# S3220A4.net
KiCad netlist of a schematic drawn in Altium Designer
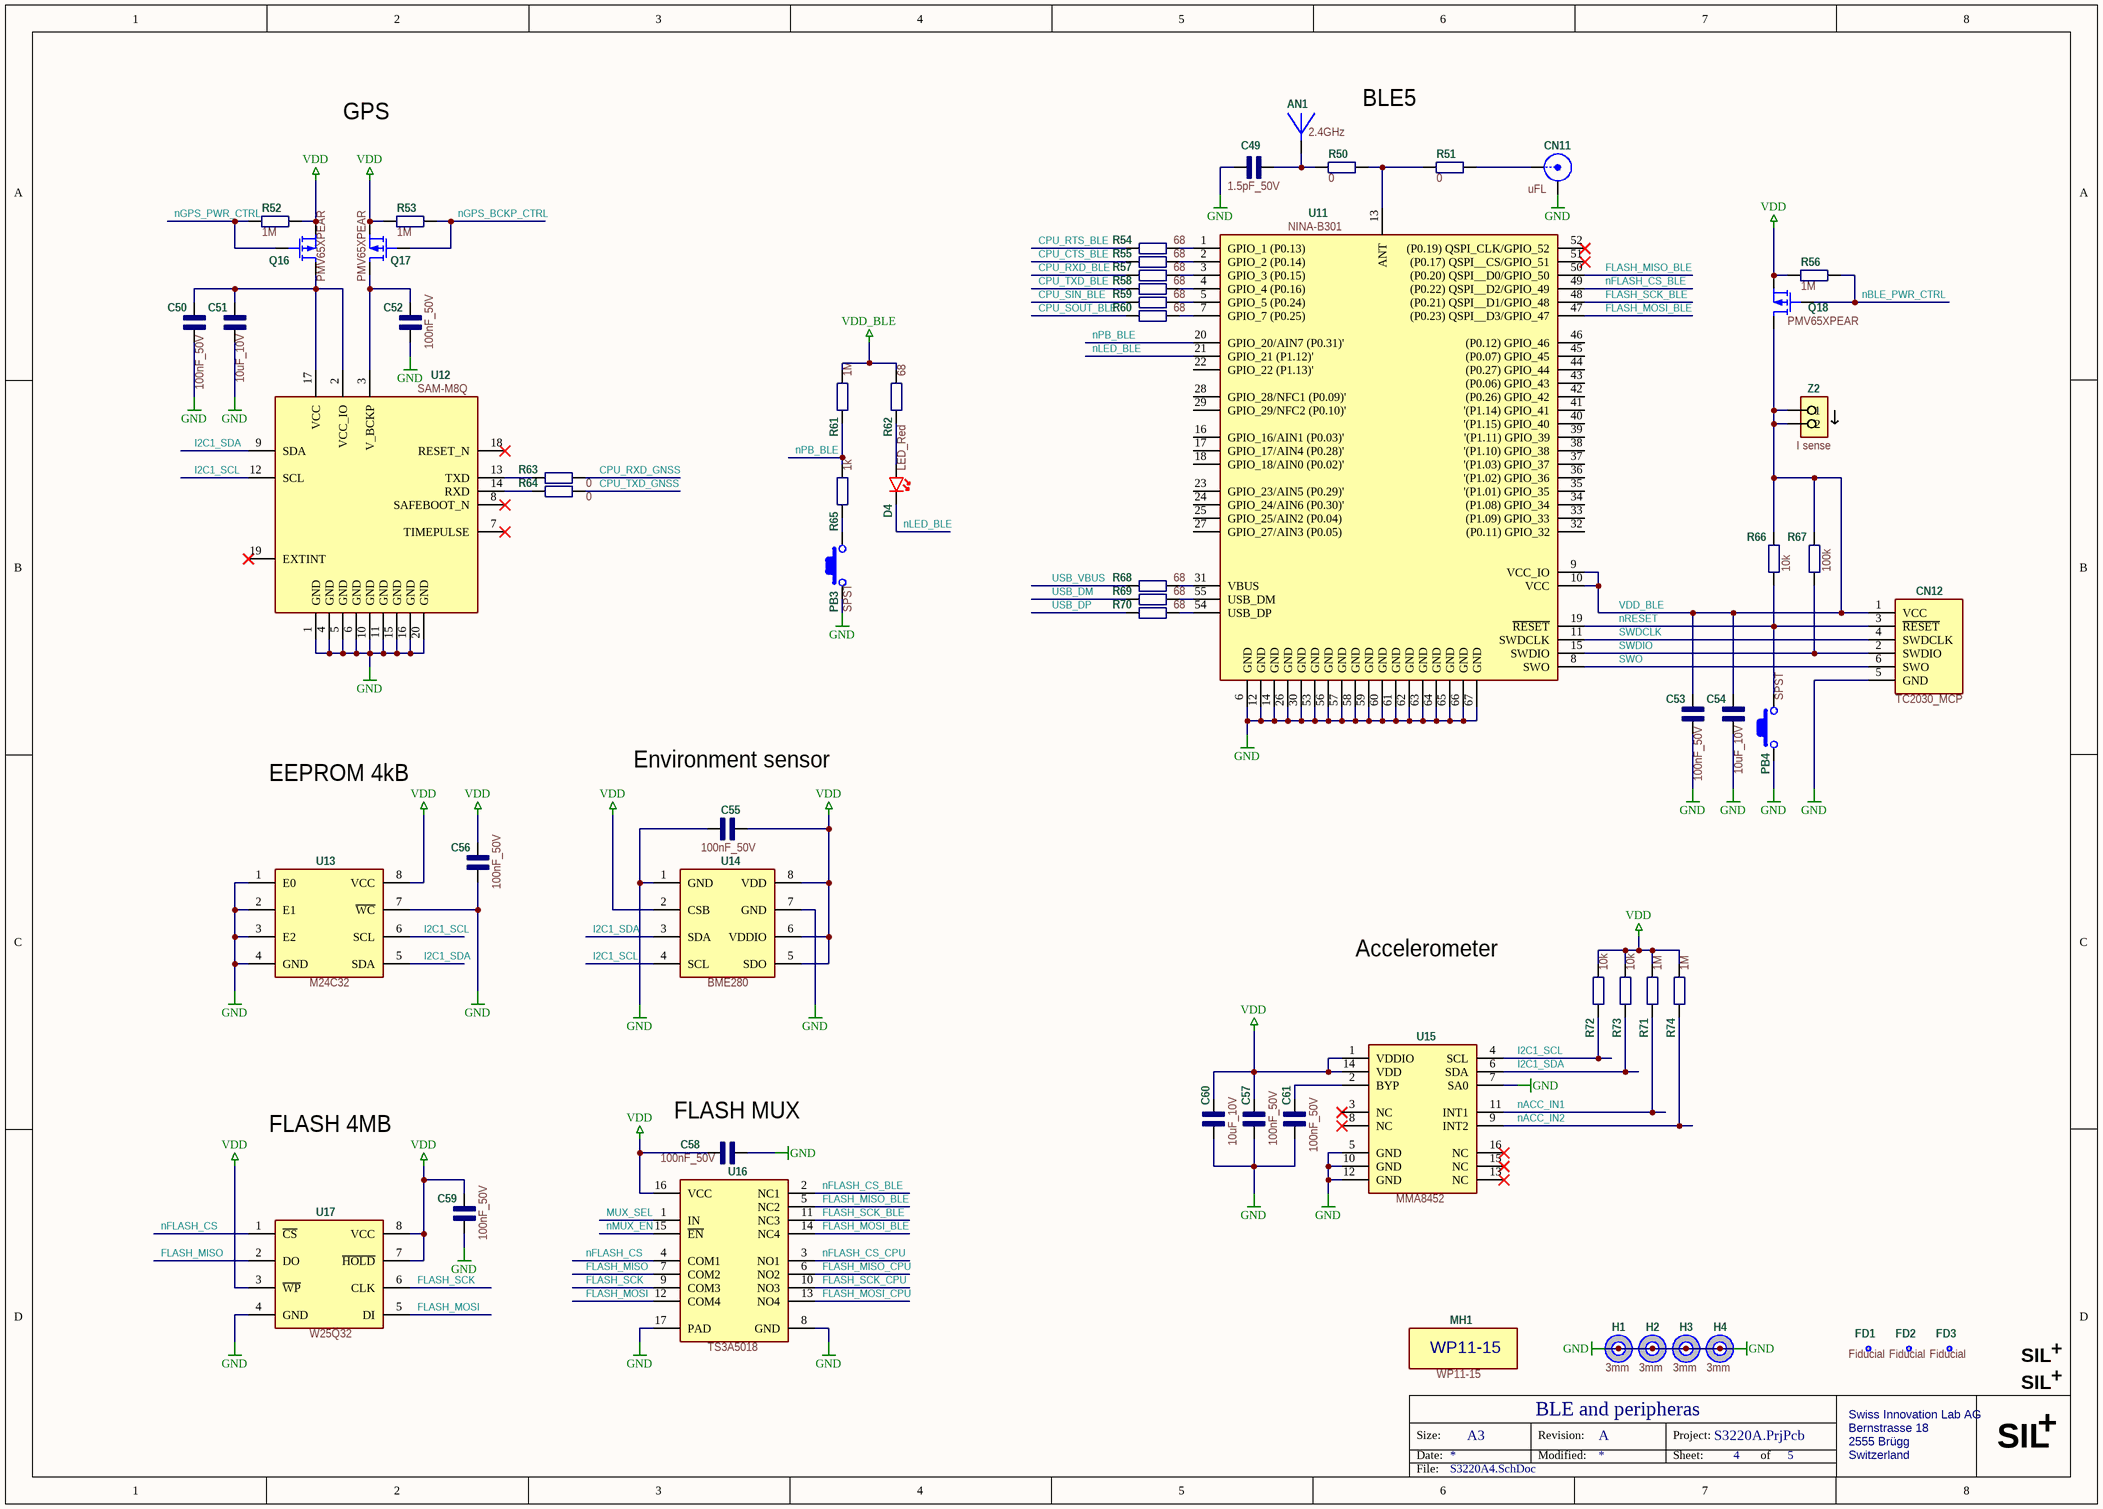
[diagram p0: S3220A4.SchDoc]

(export (version "E")
  (design (tool "Eeschema 10.0.6"))
  (components
    (comp (ref "AN1")
      (value "2.4GHz")
      (footprint "AN_2400-PCB-B")
      (description "2.4 GHz PCB antenna")
      (fields
        (field (name "MANUFACTURER") "Swiss Innovation Lab")
        (field (name "MANUFACTURER PART NUMBER") "SIL AN24GHZ")
      )
      (libsource (lib "SIL") (part "AN_2.4GHz-PCB"))
    )
    (comp (ref "C49")
      (value "1.5pF_50V")
      (footprint "SIL:C_0603")
      (description "1.5pF ±0.1pF 50V Ceramic Capacitor C0G, NP0 0603 (1608 Metric)")
      (fields
        (field (name "MANUFACTURER") "Samsung Electro-Mechanics")
        (field (name "MANUFACTURER PART NUMBER") "CL10C1R5BB8NNNC")
      )
      (libsource (lib "SIL") (part "C_1.5pF_50V"))
    )
    (comp (ref "C50")
      (value "100nF_50V")
      (footprint "SIL:C_0603")
      (description "0.1µF ±10% 50V Ceramic Capacitor X7R 0603 (1608 Metric)")
      (fields
        (field (name "MANUFACTURER") "TDK")
        (field (name "MANUFACTURER PART NUMBER") "C1608X7R1H104K080AA")
      )
      (libsource (lib "SIL") (part "C_100nF_50V"))
    )
    (comp (ref "C51")
      (value "10uF_10V")
      (footprint "SIL:C_0603")
      (description "10µF ±10% 10V Ceramic Capacitor X5R 0603 (1608 Metric)")
      (fields
        (field (name "MANUFACTURER") "Murata Electronics North America")
        (field (name "MANUFACTURER PART NUMBER") "GRM188R61A106KE69D")
      )
      (libsource (lib "SIL") (part "C_10uF_10V"))
    )
    (comp (ref "C52")
      (value "100nF_50V")
      (footprint "SIL:C_0603")
      (description "0.1µF ±10% 50V Ceramic Capacitor X7R 0603 (1608 Metric)")
      (fields
        (field (name "MANUFACTURER") "TDK")
        (field (name "MANUFACTURER PART NUMBER") "C1608X7R1H104K080AA")
      )
      (libsource (lib "SIL") (part "C_100nF_50V"))
    )
    (comp (ref "C53")
      (value "100nF_50V")
      (footprint "SIL:C_0603")
      (description "0.1µF ±10% 50V Ceramic Capacitor X7R 0603 (1608 Metric)")
      (fields
        (field (name "MANUFACTURER") "TDK")
        (field (name "MANUFACTURER PART NUMBER") "C1608X7R1H104K080AA")
      )
      (libsource (lib "SIL") (part "C_100nF_50V"))
    )
    (comp (ref "C54")
      (value "10uF_10V")
      (footprint "SIL:C_0603")
      (description "10µF ±10% 10V Ceramic Capacitor X5R 0603 (1608 Metric)")
      (fields
        (field (name "MANUFACTURER") "Murata Electronics North America")
        (field (name "MANUFACTURER PART NUMBER") "GRM188R61A106KE69D")
      )
      (libsource (lib "SIL") (part "C_10uF_10V"))
    )
    (comp (ref "C55")
      (value "100nF_50V")
      (footprint "SIL:C_0603")
      (description "0.1µF ±10% 50V Ceramic Capacitor X7R 0603 (1608 Metric)")
      (fields
        (field (name "MANUFACTURER") "TDK")
        (field (name "MANUFACTURER PART NUMBER") "C1608X7R1H104K080AA")
      )
      (libsource (lib "") (part "C_100nF_50V_3"))
    )
    (comp (ref "C56")
      (value "100nF_50V")
      (footprint "SIL:C_0603")
      (description "0.1µF ±10% 50V Ceramic Capacitor X7R 0603 (1608 Metric)")
      (fields
        (field (name "MANUFACTURER") "TDK")
        (field (name "MANUFACTURER PART NUMBER") "C1608X7R1H104K080AA")
      )
      (libsource (lib "SIL") (part "C_100nF_50V"))
    )
    (comp (ref "C57")
      (value "100nF_50V")
      (footprint "SIL:C_0603")
      (description "0.1µF ±10% 50V Ceramic Capacitor X7R 0603 (1608 Metric)")
      (fields
        (field (name "MANUFACTURER") "TDK")
        (field (name "MANUFACTURER PART NUMBER") "C1608X7R1H104K080AA")
      )
      (libsource (lib "") (part "C_100nF_50V_1"))
    )
    (comp (ref "C58")
      (value "100nF_50V")
      (footprint "SIL:C_0603")
      (description "0.1µF ±10% 50V Ceramic Capacitor X7R 0603 (1608 Metric)")
      (fields
        (field (name "MANUFACTURER") "TDK")
        (field (name "MANUFACTURER PART NUMBER") "C1608X7R1H104K080AA")
      )
      (libsource (lib "") (part "C_100nF_50V_2"))
    )
    (comp (ref "C59")
      (value "100nF_50V")
      (footprint "SIL:C_0603")
      (description "0.1µF ±10% 50V Ceramic Capacitor X7R 0603 (1608 Metric)")
      (fields
        (field (name "MANUFACTURER") "TDK")
        (field (name "MANUFACTURER PART NUMBER") "C1608X7R1H104K080AA")
      )
      (libsource (lib "SIL") (part "C_100nF_50V"))
    )
    (comp (ref "C60")
      (value "10uF_10V")
      (footprint "SIL:C_0603")
      (description "10µF ±10% 10V Ceramic Capacitor X5R 0603 (1608 Metric)")
      (fields
        (field (name "MANUFACTURER") "Murata Electronics North America")
        (field (name "MANUFACTURER PART NUMBER") "GRM188R61A106KE69D")
      )
      (libsource (lib "SIL") (part "C_10uF_10V"))
    )
    (comp (ref "C61")
      (value "100nF_50V")
      (footprint "SIL:C_0603")
      (description "0.1µF ±10% 50V Ceramic Capacitor X7R 0603 (1608 Metric)")
      (fields
        (field (name "MANUFACTURER") "TDK")
        (field (name "MANUFACTURER PART NUMBER") "C1608X7R1H104K080AA")
      )
      (libsource (lib "") (part "C_100nF_50V_1"))
    )
    (comp (ref "CN11")
      (value "uFL")
      (footprint "CN_RF_uFL")
      (description "Ultra Miniature Coaxial Connector Jack, Male Pin 50 Ohm Surface Mount Solder")
      (fields
        (field (name "MANUFACTURER") "TE Connectivity AMP Connectors")
        (field (name "MANUFACTURER PART NUMBER") "1909763-1")
      )
      (libsource (lib "SIL") (part "CN_RF_uFL"))
    )
    (comp (ref "CN12")
      (value "TC2030_MCP")
      (footprint "SIL:CN_TC2030-MCP-NL")
      (description "TC2030-MCP-NL")
      (libsource (lib "SIL") (part "CN_TC2030"))
    )
    (comp (ref "D4")
      (value "LED_Red")
      (footprint "LED_0603")
      (description "Red 631nm LED Indication - Discrete 2V 0603")
      (fields
        (field (name "MANUFACTURER") "Lite-On Inc.")
        (field (name "MANUFACTURER PART NUMBER") "LTST-C193KRKT-5A")
      )
      (libsource (lib "SIL") (part "D_LED_R_5mA"))
    )
    (comp (ref "FD1")
      (value "Fiducial")
      (footprint "FD_Fiducial")
      (description "Reference point for assembly machine")
      (fields (field (name "MANUFACTURER") "Swiss Innovation Lab"))
      (libsource (lib "SIL") (part "FD_Fiducial"))
    )
    (comp (ref "FD2")
      (value "Fiducial")
      (footprint "FD_Fiducial")
      (description "Reference point for assembly machine")
      (fields (field (name "MANUFACTURER") "Swiss Innovation Lab"))
      (libsource (lib "SIL") (part "FD_Fiducial"))
    )
    (comp (ref "FD3")
      (value "Fiducial")
      (footprint "FD_Fiducial")
      (description "Reference point for assembly machine")
      (fields (field (name "MANUFACTURER") "Swiss Innovation Lab"))
      (libsource (lib "SIL") (part "FD_Fiducial"))
    )
    (comp (ref "H1")
      (value "3mm")
      (footprint "H_3M_55M")
      (description "Hole 3mm, Pad 5.5mm")
      (fields (field (name "MANUFACTURER") "Swissinnolab"))
      (libsource (lib "Swissinnovationlab") (part "H_3M_55M"))
    )
    (comp (ref "H2")
      (value "3mm")
      (footprint "H_3M_55M")
      (description "Hole 3mm, Pad 5.5mm")
      (fields (field (name "MANUFACTURER") "Swissinnolab"))
      (libsource (lib "Swissinnovationlab") (part "H_3M_55M"))
    )
    (comp (ref "H3")
      (value "3mm")
      (footprint "H_3M_55M")
      (description "Hole 3mm, Pad 5.5mm")
      (fields (field (name "MANUFACTURER") "Swissinnolab"))
      (libsource (lib "Swissinnovationlab") (part "H_3M_55M"))
    )
    (comp (ref "H4")
      (value "3mm")
      (footprint "H_3M_55M")
      (description "Hole 3mm, Pad 5.5mm")
      (fields (field (name "MANUFACTURER") "Swissinnolab"))
      (libsource (lib "Swissinnovationlab") (part "H_3M_55M"))
    )
    (comp (ref "MH1")
      (value "WP11-15")
      (footprint "MH_WP11-15")
      (description "Case Takachi WP11-15")
      (fields (field (name "MANUFACTURER") "Takachi"))
      (libsource (lib "SIL") (part "MH_WP11-15"))
    )
    (comp (ref "PB3")
      (value "SPST")
      (footprint "SIL:PB_PTS810")
      (description "Tactile Switch SPST-NO Top Actuated Surface Mount")
      (fields
        (field (name "MANUFACTURER") "C&K")
        (field (name "MANUFACTURER PART NUMBER") "PTS810 SJM 250 SMTR LFS")
      )
      (libsource (lib "SIL") (part "PB_SPST_2.5mm"))
    )
    (comp (ref "PB4")
      (value "SPST")
      (footprint "SIL:PB_PTS810")
      (description "Tactile Switch SPST-NO Top Actuated Surface Mount")
      (fields
        (field (name "MANUFACTURER") "C&K")
        (field (name "MANUFACTURER PART NUMBER") "PTS810 SJM 250 SMTR LFS")
      )
      (libsource (lib "SIL") (part "PB_SPST_2.5mm"))
    )
    (comp (ref "Q16")
      (value "PMV65XPEAR")
      (footprint "U_SOT23-3")
      (description "P-Channel 20V 2.8A (Ta) 480mW (Ta), 6.25W (Tc) Surface Mount TO-236AB (SOT23)")
      (fields (field (name "MANUFACTURER") "Nexperia USA Inc."))
      (libsource (lib "SIL") (part "Q_PMV65"))
    )
    (comp (ref "Q17")
      (value "PMV65XPEAR")
      (footprint "U_SOT23-3")
      (description "P-Channel 20V 2.8A (Ta) 480mW (Ta), 6.25W (Tc) Surface Mount TO-236AB (SOT23)")
      (fields (field (name "MANUFACTURER") "Nexperia USA Inc."))
      (libsource (lib "SIL") (part "Q_PMV65"))
    )
    (comp (ref "Q18")
      (value "PMV65XPEAR")
      (footprint "U_SOT23-3")
      (description "P-Channel 20V 2.8A (Ta) 480mW (Ta), 6.25W (Tc) Surface Mount TO-236AB (SOT23)")
      (fields (field (name "MANUFACTURER") "Nexperia USA Inc."))
      (libsource (lib "SIL") (part "Q_PMV65"))
    )
    (comp (ref "R50")
      (value "0")
      (footprint "SIL:R_0603")
      (description "0 Ohms Jumper 0.1W, 1/10W Chip Resistor 0603 (1608 Metric) Automotive AEC-Q200 Thick Film")
      (fields
        (field (name "MANUFACTURER") "Panasonic Electronic Components")
        (field (name "MANUFACTURER PART NUMBER") "ERJ-3GEY0R00V")
      )
      (libsource (lib "SIL") (part "R_0_1%"))
    )
    (comp (ref "R51")
      (value "0")
      (footprint "SIL:R_0603")
      (description "0 Ohms Jumper 0.1W, 1/10W Chip Resistor 0603 (1608 Metric) Automotive AEC-Q200 Thick Film")
      (fields
        (field (name "MANUFACTURER") "Panasonic Electronic Components")
        (field (name "MANUFACTURER PART NUMBER") "ERJ-3GEY0R00V")
      )
      (libsource (lib "SIL") (part "R_0_1%"))
    )
    (comp (ref "R52")
      (value "1M")
      (footprint "SIL:R_0603")
      (description "1 MOhms ±1% 0.1W, 1/10W Chip Resistor 0603 (1608 Metric) Automotive AEC-Q200 Thick Film")
      (fields
        (field (name "MANUFACTURER") "Panasonic Electronic Components")
        (field (name "MANUFACTURER PART NUMBER") "ERJ-3EKF1004V")
      )
      (libsource (lib "") (part "R_1M_1%_2"))
    )
    (comp (ref "R53")
      (value "1M")
      (footprint "SIL:R_0603")
      (description "1 MOhms ±1% 0.1W, 1/10W Chip Resistor 0603 (1608 Metric) Automotive AEC-Q200 Thick Film")
      (fields
        (field (name "MANUFACTURER") "Panasonic Electronic Components")
        (field (name "MANUFACTURER PART NUMBER") "ERJ-3EKF1004V")
      )
      (libsource (lib "") (part "R_1M_1%_1"))
    )
    (comp (ref "R54")
      (value "68")
      (footprint "SIL:R_0603")
      (description "68 Ohms ±1% 0.1W, 1/10W Chip Resistor 0603 (1608 Metric) Automotive AEC-Q200 Thick Film")
      (fields
        (field (name "MANUFACTURER") "Panasonic Electronic Components")
        (field (name "MANUFACTURER PART NUMBER") "ERJ-3EKF68R0V")
      )
      (libsource (lib "SIL") (part "R_68_1%"))
    )
    (comp (ref "R55")
      (value "68")
      (footprint "SIL:R_0603")
      (description "68 Ohms ±1% 0.1W, 1/10W Chip Resistor 0603 (1608 Metric) Automotive AEC-Q200 Thick Film")
      (fields
        (field (name "MANUFACTURER") "Panasonic Electronic Components")
        (field (name "MANUFACTURER PART NUMBER") "ERJ-3EKF68R0V")
      )
      (libsource (lib "SIL") (part "R_68_1%"))
    )
    (comp (ref "R56")
      (value "1M")
      (footprint "SIL:R_0603")
      (description "1 MOhms ±1% 0.1W, 1/10W Chip Resistor 0603 (1608 Metric) Automotive AEC-Q200 Thick Film")
      (fields
        (field (name "MANUFACTURER") "Panasonic Electronic Components")
        (field (name "MANUFACTURER PART NUMBER") "ERJ-3EKF1004V")
      )
      (libsource (lib "") (part "R_1M_1%_1"))
    )
    (comp (ref "R57")
      (value "68")
      (footprint "SIL:R_0603")
      (description "68 Ohms ±1% 0.1W, 1/10W Chip Resistor 0603 (1608 Metric) Automotive AEC-Q200 Thick Film")
      (fields
        (field (name "MANUFACTURER") "Panasonic Electronic Components")
        (field (name "MANUFACTURER PART NUMBER") "ERJ-3EKF68R0V")
      )
      (libsource (lib "SIL") (part "R_68_1%"))
    )
    (comp (ref "R58")
      (value "68")
      (footprint "SIL:R_0603")
      (description "68 Ohms ±1% 0.1W, 1/10W Chip Resistor 0603 (1608 Metric) Automotive AEC-Q200 Thick Film")
      (fields
        (field (name "MANUFACTURER") "Panasonic Electronic Components")
        (field (name "MANUFACTURER PART NUMBER") "ERJ-3EKF68R0V")
      )
      (libsource (lib "SIL") (part "R_68_1%"))
    )
    (comp (ref "R59")
      (value "68")
      (footprint "SIL:R_0603")
      (description "68 Ohms ±1% 0.1W, 1/10W Chip Resistor 0603 (1608 Metric) Automotive AEC-Q200 Thick Film")
      (fields
        (field (name "MANUFACTURER") "Panasonic Electronic Components")
        (field (name "MANUFACTURER PART NUMBER") "ERJ-3EKF68R0V")
      )
      (libsource (lib "SIL") (part "R_68_1%"))
    )
    (comp (ref "R60")
      (value "68")
      (footprint "SIL:R_0603")
      (description "68 Ohms ±1% 0.1W, 1/10W Chip Resistor 0603 (1608 Metric) Automotive AEC-Q200 Thick Film")
      (fields
        (field (name "MANUFACTURER") "Panasonic Electronic Components")
        (field (name "MANUFACTURER PART NUMBER") "ERJ-3EKF68R0V")
      )
      (libsource (lib "SIL") (part "R_68_1%"))
    )
    (comp (ref "R61")
      (value "1M")
      (footprint "SIL:R_0603")
      (description "1 MOhms ±1% 0.1W, 1/10W Chip Resistor 0603 (1608 Metric) Automotive AEC-Q200 Thick Film")
      (fields
        (field (name "MANUFACTURER") "Panasonic Electronic Components")
        (field (name "MANUFACTURER PART NUMBER") "ERJ-3EKF1004V")
      )
      (libsource (lib "SIL") (part "R_1M_1%"))
    )
    (comp (ref "R62")
      (value "68")
      (footprint "SIL:R_0603")
      (description "68 Ohms ±1% 0.1W, 1/10W Chip Resistor 0603 (1608 Metric) Automotive AEC-Q200 Thick Film")
      (fields
        (field (name "MANUFACTURER") "Panasonic Electronic Components")
        (field (name "MANUFACTURER PART NUMBER") "ERJ-3EKF68R0V")
      )
      (libsource (lib "") (part "R_68_1%_1"))
    )
    (comp (ref "R63")
      (value "0")
      (footprint "SIL:R_0603")
      (description "0 Ohms Jumper 0.1W, 1/10W Chip Resistor 0603 (1608 Metric) Automotive AEC-Q200 Thick Film")
      (fields
        (field (name "MANUFACTURER") "Panasonic Electronic Components")
        (field (name "MANUFACTURER PART NUMBER") "ERJ-3GEY0R00V")
      )
      (libsource (lib "SIL") (part "R_0_1%"))
    )
    (comp (ref "R64")
      (value "0")
      (footprint "SIL:R_0603")
      (description "0 Ohms Jumper 0.1W, 1/10W Chip Resistor 0603 (1608 Metric) Automotive AEC-Q200 Thick Film")
      (fields
        (field (name "MANUFACTURER") "Panasonic Electronic Components")
        (field (name "MANUFACTURER PART NUMBER") "ERJ-3GEY0R00V")
      )
      (libsource (lib "SIL") (part "R_0_1%"))
    )
    (comp (ref "R65")
      (value "1k")
      (footprint "SIL:R_0603")
      (description "1 kOhms ±1% 0.1W, 1/10W Chip Resistor 0603 (1608 Metric) Automotive AEC-Q200 Thick Film")
      (fields
        (field (name "MANUFACTURER") "Panasonic Electronic Components")
        (field (name "MANUFACTURER PART NUMBER") "ERJ-3EKF1001V")
      )
      (libsource (lib "SIL") (part "R_1k_1%"))
    )
    (comp (ref "R66")
      (value "10k")
      (footprint "SIL:R_0603")
      (description "10 kOhms ±1% 0.1W, 1/10W Chip Resistor 0603 (1608 Metric) Automotive AEC-Q200 Thick Film")
      (fields
        (field (name "MANUFACTURER") "Panasonic Electronic Components")
        (field (name "MANUFACTURER PART NUMBER") "ERJ-3EKF1002V")
      )
      (libsource (lib "SIL") (part "R_10k_1%"))
    )
    (comp (ref "R67")
      (value "100k")
      (footprint "SIL:R_0603")
      (description "100 kOhms ±1% 0.1W, 1/10W Chip Resistor 0603 (1608 Metric) Automotive AEC-Q200 Thick Film")
      (fields
        (field (name "MANUFACTURER") "Panasonic Electronic Components")
        (field (name "MANUFACTURER PART NUMBER") "ERJ-3EKF1003V")
      )
      (libsource (lib "SIL") (part "R_100k_1%"))
    )
    (comp (ref "R68")
      (value "68")
      (footprint "SIL:R_0603")
      (description "68 Ohms ±1% 0.1W, 1/10W Chip Resistor 0603 (1608 Metric) Automotive AEC-Q200 Thick Film")
      (fields
        (field (name "MANUFACTURER") "Panasonic Electronic Components")
        (field (name "MANUFACTURER PART NUMBER") "ERJ-3EKF68R0V")
      )
      (libsource (lib "SIL") (part "R_68_1%"))
    )
    (comp (ref "R69")
      (value "68")
      (footprint "SIL:R_0603")
      (description "68 Ohms ±1% 0.1W, 1/10W Chip Resistor 0603 (1608 Metric) Automotive AEC-Q200 Thick Film")
      (fields
        (field (name "MANUFACTURER") "Panasonic Electronic Components")
        (field (name "MANUFACTURER PART NUMBER") "ERJ-3EKF68R0V")
      )
      (libsource (lib "SIL") (part "R_68_1%"))
    )
    (comp (ref "R70")
      (value "68")
      (footprint "SIL:R_0603")
      (description "68 Ohms ±1% 0.1W, 1/10W Chip Resistor 0603 (1608 Metric) Automotive AEC-Q200 Thick Film")
      (fields
        (field (name "MANUFACTURER") "Panasonic Electronic Components")
        (field (name "MANUFACTURER PART NUMBER") "ERJ-3EKF68R0V")
      )
      (libsource (lib "SIL") (part "R_68_1%"))
    )
    (comp (ref "R71")
      (value "1M")
      (footprint "SIL:R_0603")
      (description "1 MOhms ±1% 0.1W, 1/10W Chip Resistor 0603 (1608 Metric) Automotive AEC-Q200 Thick Film")
      (fields
        (field (name "MANUFACTURER") "Panasonic Electronic Components")
        (field (name "MANUFACTURER PART NUMBER") "ERJ-3EKF1004V")
      )
      (libsource (lib "SIL") (part "R_1M_1%"))
    )
    (comp (ref "R72")
      (value "10k")
      (footprint "SIL:R_0603")
      (description "10 kOhms ±1% 0.1W, 1/10W Chip Resistor 0603 (1608 Metric) Automotive AEC-Q200 Thick Film")
      (fields
        (field (name "MANUFACTURER") "Panasonic Electronic Components")
        (field (name "MANUFACTURER PART NUMBER") "ERJ-3EKF1002V")
      )
      (libsource (lib "SIL") (part "R_10k_1%"))
    )
    (comp (ref "R73")
      (value "10k")
      (footprint "SIL:R_0603")
      (description "10 kOhms ±1% 0.1W, 1/10W Chip Resistor 0603 (1608 Metric) Automotive AEC-Q200 Thick Film")
      (fields
        (field (name "MANUFACTURER") "Panasonic Electronic Components")
        (field (name "MANUFACTURER PART NUMBER") "ERJ-3EKF1002V")
      )
      (libsource (lib "SIL") (part "R_10k_1%"))
    )
    (comp (ref "R74")
      (value "1M")
      (footprint "SIL:R_0603")
      (description "1 MOhms ±1% 0.1W, 1/10W Chip Resistor 0603 (1608 Metric) Automotive AEC-Q200 Thick Film")
      (fields
        (field (name "MANUFACTURER") "Panasonic Electronic Components")
        (field (name "MANUFACTURER PART NUMBER") "ERJ-3EKF1004V")
      )
      (libsource (lib "SIL") (part "R_1M_1%"))
    )
    (comp (ref "U11")
      (value "NINA-B301")
      (footprint "U_NINA-B301")
      (description "MOD BLE 4.2 NORDIC NRF52840 SOC")
      (fields (field (name "MANUFACTURER") "uBlox"))
      (libsource (lib "SIL") (part "U_NINA-B301"))
    )
    (comp (ref "U12")
      (value "SAM-M8Q")
      (footprint "U_SAM-M8Q")
      (description "SAM-M8Q RF Receiver Galileo, GLONASS, GPS 1.575GHz, 1.602GHz -165dBm 400kbps")
      (fields
        (field (name "MANUFACTURER") "U-Blox America Inc.")
        (field (name "MANUFACTURER PART NUMBER") "SAM-M8Q-0-10")
      )
      (libsource (lib "SIL") (part "U_SAM-M8Q"))
    )
    (comp (ref "U13")
      (value "M24C32")
      (footprint "U_8-SOIC_3.9")
      (description "EEPROM Memory IC 32Kb (4K x 8) I2C 1MHz 450ns 8-SO")
      (fields
        (field (name "MANUFACTURER") "STMicroelectronics")
        (field (name "MANUFACTURER PART NUMBER") "M24C32-WMN6TP")
      )
      (libsource (lib "SIL") (part "U_M24C32"))
    )
    (comp (ref "U14")
      (value "BME280")
      (footprint "SIL:U_BME280")
      (description "Humidity Temperature Sensor 0 ~ 100% RH I2C, SPI ±3% 1s Surface Mount")
      (fields (field (name "MANUFACTURER") "Bosch Sensortec"))
      (libsource (lib "SIL") (part "U_BME280"))
    )
    (comp (ref "U15")
      (value "MMA8452")
      (footprint "U_16-QFN-5X3")
      (description "Accelerometer X, Y, Z Axis ±2g, 4g, 8g 0.78Hz ~ 400Hz 16-QFN (3x3)")
      (fields
        (field (name "MANUFACTURER") "NXP USA Inc.")
        (field (name "MANUFACTURER PART NUMBER") "MMA8452QT")
      )
      (libsource (lib "SIL") (part "U_MMA8452"))
    )
    (comp (ref "U16")
      (value "TS3A5018")
      (footprint "U_16-VFQFN")
      (description "4 Circuit IC Switch 2:1 10Ohm 16-UQFN (2.6x1.8)")
      (fields
        (field (name "MANUFACTURER") "Texas Instruments")
        (field (name "MANUFACTURER PART NUMBER") "TS3A5018RGYR")
      )
      (libsource (lib "SIL") (part "U_TS3A5018"))
    )
    (comp (ref "U17")
      (value "W25Q32")
      (footprint "U_8-SOIC_5.3")
      (description "FLASH - NOR Memory IC 32Mb (4M x 8) SPI - Quad I/O 133MHz  8-SOIC")
      (fields
        (field (name "MANUFACTURER") "Winbond Electronics")
        (field (name "MANUFACTURER PART NUMBER") "W25Q32JVSSIQ")
      )
      (libsource (lib "SIL") (part "U_W25Q32"))
    )
    (comp (ref "Z2")
      (value "I sense")
      (footprint "Z_I_SENSE")
      (description "2 Positions Header Connector 0.100\" (2.54mm) SMD Gold for current measurement")
      (fields (field (name "MANUFACTURER") "SIL"))
      (libsource (lib "SIL") (part "Z_I_sense"))
    )
    (comp (ref "Z3")
      (value "SIL logo")
      (footprint "Z_SIL-logo")
      (fields
        (field (name "MANUFACTURER") "Swiss Innovation Lab")
        (field (name "MANUFACTURER PART NUMBER") "SIL Logo")
      )
      (libsource (lib "SIL") (part "Z_SIL_logo"))
    )
    (comp (ref "Z4")
      (value "SIL logo")
      (footprint "Z_SIL-logo")
      (fields
        (field (name "MANUFACTURER") "Swiss Innovation Lab")
        (field (name "MANUFACTURER PART NUMBER") "SIL Logo")
      )
      (libsource (lib "SIL") (part "Z_SIL_logo"))
    )
  )
  (nets
    (net (code "1") (name "/CPU_CTS_BLE") (class "Default")
      (node (ref "R55") (pin "1") (pinfunction "1_1") (pintype "passive"))
    )
    (net (code "2") (name "/CPU_RTS_BLE") (class "Default")
      (node (ref "R54") (pin "1") (pinfunction "1_1") (pintype "passive"))
    )
    (net (code "3") (name "/CPU_RXD_BLE") (class "Default")
      (node (ref "R57") (pin "1") (pinfunction "1_1") (pintype "passive"))
    )
    (net (code "4") (name "/CPU_RXD_GNSS") (class "Default")
      (node (ref "R63") (pin "2") (pinfunction "2_2") (pintype "passive"))
    )
    (net (code "5") (name "/CPU_SIN_BLE") (class "Default")
      (node (ref "R59") (pin "1") (pinfunction "1_1") (pintype "passive"))
    )
    (net (code "6") (name "/CPU_SOUT_BLE") (class "Default")
      (node (ref "R60") (pin "1") (pinfunction "1_1") (pintype "passive"))
    )
    (net (code "7") (name "/CPU_TXD_BLE") (class "Default")
      (node (ref "R58") (pin "1") (pinfunction "1_1") (pintype "passive"))
    )
    (net (code "8") (name "/CPU_TXD_GNSS") (class "Default")
      (node (ref "R64") (pin "2") (pinfunction "2_2") (pintype "passive"))
    )
    (net (code "9") (name "/FLASH_MISO") (class "Default")
      (node (ref "U16") (pin "7") (pinfunction "COM2_7") (pintype "passive"))
      (node (ref "U17") (pin "2") (pinfunction "DO_2") (pintype "passive"))
    )
    (net (code "10") (name "/FLASH_MISO_BLE") (class "Default")
      (node (ref "U11") (pin "50") (pinfunction "(P0.20)_QSPI__D0/GPIO_50_50") (pintype "passive"))
      (node (ref "U16") (pin "5") (pinfunction "NC2_5") (pintype "passive"))
    )
    (net (code "11") (name "/FLASH_MISO_CPU") (class "Default")
      (node (ref "U16") (pin "6") (pinfunction "NO2_6") (pintype "passive"))
    )
    (net (code "12") (name "/FLASH_MOSI") (class "Default")
      (node (ref "U16") (pin "12") (pinfunction "COM4_12") (pintype "passive"))
      (node (ref "U17") (pin "5") (pinfunction "DI_5") (pintype "passive"))
    )
    (net (code "13") (name "/FLASH_MOSI_BLE") (class "Default")
      (node (ref "U11") (pin "47") (pinfunction "(P0.23)_QSPI__D3/GPIO_47_47") (pintype "passive"))
      (node (ref "U16") (pin "14") (pinfunction "NC4_14") (pintype "passive"))
    )
    (net (code "14") (name "/FLASH_MOSI_CPU") (class "Default")
      (node (ref "U16") (pin "13") (pinfunction "NO4_13") (pintype "passive"))
    )
    (net (code "15") (name "/FLASH_SCK") (class "Default")
      (node (ref "U16") (pin "9") (pinfunction "COM3_9") (pintype "passive"))
      (node (ref "U17") (pin "6") (pinfunction "CLK_6") (pintype "passive"))
    )
    (net (code "16") (name "/FLASH_SCK_BLE") (class "Default")
      (node (ref "U11") (pin "48") (pinfunction "(P0.21)_QSPI__D1/GPIO_48_48") (pintype "passive"))
      (node (ref "U16") (pin "11") (pinfunction "NC3_11") (pintype "passive"))
    )
    (net (code "17") (name "/FLASH_SCK_CPU") (class "Default")
      (node (ref "U16") (pin "10") (pinfunction "NO3_10") (pintype "passive"))
    )
    (net (code "18") (name "/I2C1_SCL") (class "Default")
      (node (ref "R72") (pin "1") (pinfunction "1_1") (pintype "passive"))
      (node (ref "U12") (pin "12") (pinfunction "SCL_12") (pintype "passive"))
      (node (ref "U13") (pin "6") (pinfunction "SCL_6") (pintype "passive"))
      (node (ref "U14") (pin "4") (pinfunction "SCL_4") (pintype "passive"))
      (node (ref "U15") (pin "4") (pinfunction "SCL_4") (pintype "passive"))
    )
    (net (code "19") (name "/I2C1_SDA") (class "Default")
      (node (ref "R73") (pin "1") (pinfunction "1_1") (pintype "passive"))
      (node (ref "U12") (pin "9") (pinfunction "SDA_9") (pintype "passive"))
      (node (ref "U13") (pin "5") (pinfunction "SDA_5") (pintype "passive"))
      (node (ref "U14") (pin "3") (pinfunction "SDA_3") (pintype "passive"))
      (node (ref "U15") (pin "6") (pinfunction "SDA_6") (pintype "passive"))
    )
    (net (code "20") (name "/MUX_SEL") (class "Default")
      (node (ref "U16") (pin "1") (pinfunction "IN_1") (pintype "passive"))
    )
    (net (code "21") (name "/SWDCLK") (class "Default")
      (node (ref "CN12") (pin "4") (pinfunction "SWDCLK_4") (pintype "passive"))
      (node (ref "U11") (pin "11") (pinfunction "SWDCLK_11") (pintype "passive"))
    )
    (net (code "22") (name "/SWDIO") (class "Default")
      (node (ref "CN12") (pin "2") (pinfunction "SWDIO_2") (pintype "passive"))
      (node (ref "R67") (pin "1") (pinfunction "1_1") (pintype "passive"))
      (node (ref "U11") (pin "15") (pinfunction "SWDIO_15") (pintype "passive"))
    )
    (net (code "23") (name "/SWO") (class "Default")
      (node (ref "CN12") (pin "6") (pinfunction "SWO_6") (pintype "passive"))
      (node (ref "U11") (pin "8") (pinfunction "SWO_8") (pintype "passive"))
    )
    (net (code "24") (name "/USB_DM") (class "Default")
      (node (ref "R69") (pin "1") (pinfunction "1_1") (pintype "passive"))
    )
    (net (code "25") (name "/USB_DP") (class "Default")
      (node (ref "R70") (pin "1") (pinfunction "1_1") (pintype "passive"))
    )
    (net (code "26") (name "/USB_VBUS") (class "Default")
      (node (ref "R68") (pin "1") (pinfunction "1_1") (pintype "passive"))
    )
    (net (code "27") (name "/nACC_IN1") (class "Default")
      (node (ref "R71") (pin "2") (pinfunction "2_2") (pintype "passive"))
      (node (ref "U15") (pin "11") (pinfunction "INT1_11") (pintype "passive"))
    )
    (net (code "28") (name "/nACC_IN2") (class "Default")
      (node (ref "R74") (pin "2") (pinfunction "2_2") (pintype "passive"))
      (node (ref "U15") (pin "9") (pinfunction "INT2_9") (pintype "passive"))
    )
    (net (code "29") (name "/nBLE_PWR_CTRL") (class "Default")
      (node (ref "Q18") (pin "1") (pinfunction "G_1") (pintype "passive"))
      (node (ref "R56") (pin "1") (pinfunction "1_1") (pintype "passive"))
    )
    (net (code "30") (name "/nFLASH_CS") (class "Default")
      (node (ref "U16") (pin "4") (pinfunction "COM1_4") (pintype "passive"))
      (node (ref "U17") (pin "1") (pinfunction "~{CS}_1") (pintype "passive"))
    )
    (net (code "31") (name "/nFLASH_CS_BLE") (class "Default")
      (node (ref "U11") (pin "49") (pinfunction "(P0.22)_QSPI__D2/GPIO_49_49") (pintype "passive"))
      (node (ref "U16") (pin "2") (pinfunction "NC1_2") (pintype "passive"))
    )
    (net (code "32") (name "/nFLASH_CS_CPU") (class "Default")
      (node (ref "U16") (pin "3") (pinfunction "NO1_3") (pintype "passive"))
    )
    (net (code "33") (name "/nGPS_BCKP_CTRL") (class "Default")
      (node (ref "Q17") (pin "1") (pinfunction "G_1") (pintype "passive"))
      (node (ref "R53") (pin "1") (pinfunction "1_1") (pintype "passive"))
    )
    (net (code "34") (name "/nGPS_PWR_CTRL") (class "Default")
      (node (ref "Q16") (pin "1") (pinfunction "G_1") (pintype "passive"))
      (node (ref "R52") (pin "1") (pinfunction "1_1") (pintype "passive"))
    )
    (net (code "35") (name "/nLED_BLE") (class "Default")
      (node (ref "D4") (pin "2") (pinfunction "K_2") (pintype "passive"))
      (node (ref "U11") (pin "21") (pinfunction "GPIO_21_(P1.12)'_21") (pintype "passive"))
    )
    (net (code "36") (name "/nMUX_EN") (class "Default")
      (node (ref "U16") (pin "15") (pinfunction "~{EN}_15") (pintype "passive"))
    )
    (net (code "37") (name "/nPB_BLE") (class "Default")
      (node (ref "R61") (pin "2") (pinfunction "2_2") (pintype "passive"))
      (node (ref "R65") (pin "2") (pinfunction "2_2") (pintype "passive"))
      (node (ref "U11") (pin "20") (pinfunction "GPIO_20/AIN7_(P0.31)'_20") (pintype "passive"))
    )
    (net (code "38") (name "/nRESET") (class "Default")
      (node (ref "CN12") (pin "3") (pinfunction "~{RESET}_3") (pintype "passive"))
      (node (ref "PB4") (pin "2") (pinfunction "2_2") (pintype "passive"))
      (node (ref "R66") (pin "1") (pinfunction "1_1") (pintype "passive"))
      (node (ref "U11") (pin "19") (pinfunction "~{RESET}_19") (pintype "passive"))
    )
    (net (code "39") (name "GND") (class "Default")
      (node (ref "C49") (pin "1") (pintype "passive"))
      (node (ref "C50") (pin "1") (pintype "passive"))
      (node (ref "C51") (pin "1") (pintype "passive"))
      (node (ref "C52") (pin "1") (pintype "passive"))
      (node (ref "C53") (pin "1") (pintype "passive"))
      (node (ref "C54") (pin "1") (pintype "passive"))
      (node (ref "C55") (pin "2") (pintype "passive"))
      (node (ref "C56") (pin "1") (pintype "passive"))
      (node (ref "C57") (pin "2") (pintype "passive"))
      (node (ref "C58") (pin "2") (pintype "passive"))
      (node (ref "C59") (pin "1") (pintype "passive"))
      (node (ref "C60") (pin "1") (pintype "passive"))
      (node (ref "C61") (pin "2") (pintype "passive"))
      (node (ref "CN11") (pin "G") (pinfunction "G_G") (pintype "passive"))
      (node (ref "CN12") (pin "5") (pinfunction "GND_5") (pintype "passive"))
      (node (ref "H1") (pin "0") (pinfunction "0_0") (pintype "passive"))
      (node (ref "H2") (pin "0") (pinfunction "0_0") (pintype "passive"))
      (node (ref "H3") (pin "0") (pinfunction "0_0") (pintype "passive"))
      (node (ref "H4") (pin "0") (pinfunction "0_0") (pintype "passive"))
      (node (ref "PB3") (pin "2") (pinfunction "2_2") (pintype "passive"))
      (node (ref "PB4") (pin "1") (pinfunction "1_1") (pintype "passive"))
      (node (ref "U11") (pin "12") (pinfunction "GND_12") (pintype "power_in"))
      (node (ref "U11") (pin "14") (pinfunction "GND_14") (pintype "power_in"))
      (node (ref "U11") (pin "26") (pinfunction "GND_26") (pintype "power_in"))
      (node (ref "U11") (pin "30") (pinfunction "GND_30") (pintype "power_in"))
      (node (ref "U11") (pin "53") (pinfunction "GND_53") (pintype "power_in"))
      (node (ref "U11") (pin "56") (pinfunction "GND_56") (pintype "power_in"))
      (node (ref "U11") (pin "57") (pinfunction "GND_57") (pintype "passive"))
      (node (ref "U11") (pin "58") (pinfunction "GND_58") (pintype "power_in"))
      (node (ref "U11") (pin "59") (pinfunction "GND_59") (pintype "power_in"))
      (node (ref "U11") (pin "6") (pinfunction "GND_6") (pintype "power_in"))
      (node (ref "U11") (pin "60") (pinfunction "GND_60") (pintype "power_in"))
      (node (ref "U11") (pin "61") (pinfunction "GND_61") (pintype "power_in"))
      (node (ref "U11") (pin "62") (pinfunction "GND_62") (pintype "power_in"))
      (node (ref "U11") (pin "63") (pinfunction "GND_63") (pintype "power_in"))
      (node (ref "U11") (pin "64") (pinfunction "GND_64") (pintype "power_in"))
      (node (ref "U11") (pin "65") (pinfunction "GND_65") (pintype "power_in"))
      (node (ref "U11") (pin "66") (pinfunction "GND_66") (pintype "power_in"))
      (node (ref "U11") (pin "67") (pinfunction "GND_67") (pintype "power_in"))
      (node (ref "U12") (pin "1") (pinfunction "GND_1") (pintype "passive"))
      (node (ref "U12") (pin "10") (pinfunction "GND_10") (pintype "passive"))
      (node (ref "U12") (pin "11") (pinfunction "GND_11") (pintype "passive"))
      (node (ref "U12") (pin "15") (pinfunction "GND_15") (pintype "passive"))
      (node (ref "U12") (pin "16") (pinfunction "GND_16") (pintype "passive"))
      (node (ref "U12") (pin "20") (pinfunction "GND_20") (pintype "passive"))
      (node (ref "U12") (pin "4") (pinfunction "GND_4") (pintype "passive"))
      (node (ref "U12") (pin "5") (pinfunction "GND_5") (pintype "passive"))
      (node (ref "U12") (pin "6") (pinfunction "GND_6") (pintype "passive"))
      (node (ref "U13") (pin "1") (pinfunction "E0_1") (pintype "passive"))
      (node (ref "U13") (pin "2") (pinfunction "E1_2") (pintype "passive"))
      (node (ref "U13") (pin "3") (pinfunction "E2_3") (pintype "passive"))
      (node (ref "U13") (pin "4") (pinfunction "GND_4") (pintype "power_in"))
      (node (ref "U13") (pin "7") (pinfunction "~{WC}_7") (pintype "passive"))
      (node (ref "U14") (pin "1") (pinfunction "GND_1") (pintype "power_in"))
      (node (ref "U14") (pin "7") (pinfunction "GND_7") (pintype "power_in"))
      (node (ref "U15") (pin "10") (pinfunction "GND_10") (pintype "power_in"))
      (node (ref "U15") (pin "12") (pinfunction "GND_12") (pintype "power_in"))
      (node (ref "U15") (pin "5") (pinfunction "GND_5") (pintype "power_in"))
      (node (ref "U15") (pin "7") (pinfunction "SA0_7") (pintype "passive"))
      (node (ref "U16") (pin "17") (pinfunction "PAD_17") (pintype "power_in"))
      (node (ref "U16") (pin "8") (pinfunction "GND_8") (pintype "power_in"))
      (node (ref "U17") (pin "4") (pinfunction "GND_4") (pintype "power_in"))
    )
    (net (code "40") (name "Net-(AN1-Pad1)") (class "Default")
      (node (ref "AN1") (pin "1") (pintype "passive"))
      (node (ref "C49") (pin "2") (pintype "passive"))
      (node (ref "R50") (pin "1") (pinfunction "1_1") (pintype "passive"))
    )
    (net (code "41") (name "Net-(CN11-PadS)") (class "Default")
      (node (ref "CN11") (pin "S") (pinfunction "S_S") (pintype "passive"))
      (node (ref "R51") (pin "2") (pinfunction "2_2") (pintype "passive"))
    )
    (net (code "42") (name "Net-(D4-A)") (class "Default")
      (node (ref "D4") (pin "1") (pinfunction "A_1") (pintype "passive"))
      (node (ref "R62") (pin "1") (pinfunction "1_1") (pintype "passive"))
    )
    (net (code "43") (name "Net-(PB3-Pad1)") (class "Default")
      (node (ref "PB3") (pin "1") (pinfunction "1_1") (pintype "passive"))
      (node (ref "R65") (pin "1") (pinfunction "1_1") (pintype "passive"))
    )
    (net (code "44") (name "Net-(Q16-D)") (class "Default")
      (node (ref "C50") (pin "2") (pintype "passive"))
      (node (ref "C51") (pin "2") (pintype "passive"))
      (node (ref "Q16") (pin "3") (pinfunction "D_3") (pintype "passive"))
      (node (ref "U12") (pin "17") (pinfunction "VCC_17") (pintype "passive"))
      (node (ref "U12") (pin "2") (pinfunction "VCC_IO_2") (pintype "passive"))
    )
    (net (code "45") (name "Net-(Q17-D)") (class "Default")
      (node (ref "C52") (pin "2") (pintype "passive"))
      (node (ref "Q17") (pin "3") (pinfunction "D_3") (pintype "passive"))
      (node (ref "U12") (pin "3") (pinfunction "V_BCKP_3") (pintype "passive"))
    )
    (net (code "46") (name "Net-(U11-ANT)") (class "Default")
      (node (ref "R50") (pin "2") (pinfunction "2_2") (pintype "passive"))
      (node (ref "R51") (pin "1") (pinfunction "1_1") (pintype "passive"))
      (node (ref "U11") (pin "13") (pinfunction "ANT_13") (pintype "passive"))
    )
    (net (code "47") (name "Net-(U11-GPIO_1_(P0.13))") (class "Default")
      (node (ref "R54") (pin "2") (pinfunction "2_2") (pintype "passive"))
      (node (ref "U11") (pin "1") (pinfunction "GPIO_1_(P0.13)_1") (pintype "passive"))
    )
    (net (code "48") (name "Net-(U11-GPIO_2_(P0.14))") (class "Default")
      (node (ref "R55") (pin "2") (pinfunction "2_2") (pintype "passive"))
      (node (ref "U11") (pin "2") (pinfunction "GPIO_2_(P0.14)_2") (pintype "passive"))
    )
    (net (code "49") (name "Net-(U11-GPIO_3_(P0.15))") (class "Default")
      (node (ref "R57") (pin "2") (pinfunction "2_2") (pintype "passive"))
      (node (ref "U11") (pin "3") (pinfunction "GPIO_3_(P0.15)_3") (pintype "passive"))
    )
    (net (code "50") (name "Net-(U11-GPIO_4_(P0.16))") (class "Default")
      (node (ref "R58") (pin "2") (pinfunction "2_2") (pintype "passive"))
      (node (ref "U11") (pin "4") (pinfunction "GPIO_4_(P0.16)_4") (pintype "passive"))
    )
    (net (code "51") (name "Net-(U11-GPIO_5_(P0.24))") (class "Default")
      (node (ref "R59") (pin "2") (pinfunction "2_2") (pintype "passive"))
      (node (ref "U11") (pin "5") (pinfunction "GPIO_5_(P0.24)_5") (pintype "passive"))
    )
    (net (code "52") (name "Net-(U11-GPIO_7_(P0.25))") (class "Default")
      (node (ref "R60") (pin "2") (pinfunction "2_2") (pintype "passive"))
      (node (ref "U11") (pin "7") (pinfunction "GPIO_7_(P0.25)_7") (pintype "passive"))
    )
    (net (code "53") (name "Net-(U11-USB_DM)") (class "Default")
      (node (ref "R69") (pin "2") (pinfunction "2_2") (pintype "passive"))
      (node (ref "U11") (pin "55") (pinfunction "USB_DM_55") (pintype "passive"))
    )
    (net (code "54") (name "Net-(U11-USB_DP)") (class "Default")
      (node (ref "R70") (pin "2") (pinfunction "2_2") (pintype "passive"))
      (node (ref "U11") (pin "54") (pinfunction "USB_DP_54") (pintype "passive"))
    )
    (net (code "55") (name "Net-(U11-VBUS)") (class "Default")
      (node (ref "R68") (pin "2") (pinfunction "2_2") (pintype "passive"))
      (node (ref "U11") (pin "31") (pinfunction "VBUS_31") (pintype "passive"))
    )
    (net (code "56") (name "Net-(U12-RXD)") (class "Default")
      (node (ref "R64") (pin "1") (pinfunction "1_1") (pintype "passive"))
      (node (ref "U12") (pin "14") (pinfunction "RXD_14") (pintype "passive"))
    )
    (net (code "57") (name "Net-(U12-TXD)") (class "Default")
      (node (ref "R63") (pin "1") (pinfunction "1_1") (pintype "passive"))
      (node (ref "U12") (pin "13") (pinfunction "TXD_13") (pintype "passive"))
    )
    (net (code "58") (name "Net-(U15-BYP)") (class "Default")
      (node (ref "C61") (pin "1") (pintype "passive"))
      (node (ref "U15") (pin "2") (pinfunction "BYP_2") (pintype "passive"))
    )
    (net (code "59") (name "VDD") (class "Default")
      (node (ref "C55") (pin "1") (pintype "passive"))
      (node (ref "C56") (pin "2") (pintype "passive"))
      (node (ref "C57") (pin "1") (pintype "passive"))
      (node (ref "C58") (pin "1") (pintype "passive"))
      (node (ref "C59") (pin "2") (pintype "passive"))
      (node (ref "C60") (pin "2") (pintype "passive"))
      (node (ref "Q16") (pin "2") (pinfunction "S_2") (pintype "passive"))
      (node (ref "Q17") (pin "2") (pinfunction "S_2") (pintype "passive"))
      (node (ref "Q18") (pin "2") (pinfunction "S_2") (pintype "passive"))
      (node (ref "R52") (pin "2") (pinfunction "2_2") (pintype "passive"))
      (node (ref "R53") (pin "2") (pinfunction "2_2") (pintype "passive"))
      (node (ref "R56") (pin "2") (pinfunction "2_2") (pintype "passive"))
      (node (ref "R71") (pin "1") (pinfunction "1_1") (pintype "passive"))
      (node (ref "R72") (pin "2") (pinfunction "2_2") (pintype "passive"))
      (node (ref "R73") (pin "2") (pinfunction "2_2") (pintype "passive"))
      (node (ref "R74") (pin "1") (pinfunction "1_1") (pintype "passive"))
      (node (ref "U13") (pin "8") (pinfunction "VCC_8") (pintype "power_in"))
      (node (ref "U14") (pin "2") (pinfunction "CSB_2") (pintype "passive"))
      (node (ref "U14") (pin "5") (pinfunction "SDO_5") (pintype "passive"))
      (node (ref "U14") (pin "6") (pinfunction "VDDIO_6") (pintype "power_in"))
      (node (ref "U14") (pin "8") (pinfunction "VDD_8") (pintype "power_in"))
      (node (ref "U15") (pin "1") (pinfunction "VDDIO_1") (pintype "power_in"))
      (node (ref "U15") (pin "14") (pinfunction "VDD_14") (pintype "power_in"))
      (node (ref "U16") (pin "16") (pinfunction "VCC_16") (pintype "power_in"))
      (node (ref "U17") (pin "3") (pinfunction "~{WP}_3") (pintype "passive"))
      (node (ref "U17") (pin "7") (pinfunction "~{HOLD}_7") (pintype "passive"))
      (node (ref "U17") (pin "8") (pinfunction "VCC_8") (pintype "power_in"))
    )
    (net (code "60") (name "VDD_BLE") (class "Default")
      (node (ref "C53") (pin "2") (pintype "passive"))
      (node (ref "C54") (pin "2") (pintype "passive"))
      (node (ref "CN12") (pin "1") (pinfunction "VCC_1") (pintype "power_in"))
      (node (ref "Q18") (pin "3") (pinfunction "D_3") (pintype "passive"))
      (node (ref "R61") (pin "1") (pinfunction "1_1") (pintype "passive"))
      (node (ref "R62") (pin "2") (pinfunction "2_2") (pintype "passive"))
      (node (ref "R66") (pin "2") (pinfunction "2_2") (pintype "passive"))
      (node (ref "R67") (pin "2") (pinfunction "2_2") (pintype "passive"))
      (node (ref "U11") (pin "10") (pinfunction "VCC_10") (pintype "power_in"))
      (node (ref "U11") (pin "9") (pinfunction "VCC_IO_9") (pintype "power_in"))
      (node (ref "Z2") (pin "1") (pinfunction "1_1") (pintype "passive"))
      (node (ref "Z2") (pin "2") (pinfunction "2_2") (pintype "passive"))
    )
    (net (code "61") (name "unconnected-(FD1-Pad0)") (class "Default")
      (node (ref "FD1") (pin "0") (pinfunction "0_0") (pintype "passive"))
    )
    (net (code "62") (name "unconnected-(FD2-Pad0)") (class "Default")
      (node (ref "FD2") (pin "0") (pinfunction "0_0") (pintype "passive"))
    )
    (net (code "63") (name "unconnected-(FD3-Pad0)") (class "Default")
      (node (ref "FD3") (pin "0") (pinfunction "0_0") (pintype "passive"))
    )
    (net (code "64") (name "unconnected-(MH1-Pad0)") (class "Default")
      (node (ref "MH1") (pin "0") (pinfunction "0_0") (pintype "passive"))
    )
    (net (code "65") (name "unconnected-(U11-'(P1.01)_GPIO_35-Pad35)") (class "Default")
      (node (ref "U11") (pin "35") (pinfunction "'(P1.01)_GPIO_35_35") (pintype "passive"))
    )
    (net (code "66") (name "unconnected-(U11-'(P1.02)_GPIO_36-Pad36)") (class "Default")
      (node (ref "U11") (pin "36") (pinfunction "'(P1.02)_GPIO_36_36") (pintype "passive"))
    )
    (net (code "67") (name "unconnected-(U11-'(P1.03)_GPIO_37-Pad37)") (class "Default")
      (node (ref "U11") (pin "37") (pinfunction "'(P1.03)_GPIO_37_37") (pintype "passive"))
    )
    (net (code "68") (name "unconnected-(U11-'(P1.10)_GPIO_38-Pad38)") (class "Default")
      (node (ref "U11") (pin "38") (pinfunction "'(P1.10)_GPIO_38_38") (pintype "passive"))
    )
    (net (code "69") (name "unconnected-(U11-'(P1.11)_GPIO_39-Pad39)") (class "Default")
      (node (ref "U11") (pin "39") (pinfunction "'(P1.11)_GPIO_39_39") (pintype "passive"))
    )
    (net (code "70") (name "unconnected-(U11-'(P1.14)_GPIO_41-Pad41)") (class "Default")
      (node (ref "U11") (pin "41") (pinfunction "'(P1.14)_GPIO_41_41") (pintype "passive"))
    )
    (net (code "71") (name "unconnected-(U11-'(P1.15)_GPIO_40-Pad40)") (class "Default")
      (node (ref "U11") (pin "40") (pinfunction "'(P1.15)_GPIO_40_40") (pintype "passive"))
    )
    (net (code "72") (name "unconnected-(U11-(P0.06)_GPIO_43-Pad43)") (class "Default")
      (node (ref "U11") (pin "43") (pinfunction "(P0.06)_GPIO_43_43") (pintype "passive"))
    )
    (net (code "73") (name "unconnected-(U11-(P0.07)_GPIO_45-Pad45)") (class "Default")
      (node (ref "U11") (pin "45") (pinfunction "(P0.07)_GPIO_45_45") (pintype "passive"))
    )
    (net (code "74") (name "unconnected-(U11-(P0.11)_GPIO_32-Pad32)") (class "Default")
      (node (ref "U11") (pin "32") (pinfunction "(P0.11)_GPIO_32_32") (pintype "passive"))
    )
    (net (code "75") (name "unconnected-(U11-(P0.12)_GPIO_46-Pad46)") (class "Default")
      (node (ref "U11") (pin "46") (pinfunction "(P0.12)_GPIO_46_46") (pintype "passive"))
    )
    (net (code "76") (name "unconnected-(U11-(P0.17)_QSPI__CS{slash}GPIO_51-Pad51)") (class "Default")
      (node (ref "U11") (pin "51") (pinfunction "(P0.17)_QSPI__CS/GPIO_51_51") (pintype "passive+no_connect"))
    )
    (net (code "77") (name "unconnected-(U11-(P0.19)_QSPI_CLK{slash}GPIO_52-Pad52)") (class "Default")
      (node (ref "U11") (pin "52") (pinfunction "(P0.19)_QSPI_CLK/GPIO_52_52") (pintype "passive+no_connect"))
    )
    (net (code "78") (name "unconnected-(U11-(P0.26)_GPIO_42-Pad42)") (class "Default")
      (node (ref "U11") (pin "42") (pinfunction "(P0.26)_GPIO_42_42") (pintype "passive"))
    )
    (net (code "79") (name "unconnected-(U11-(P0.27)_GPIO_44-Pad44)") (class "Default")
      (node (ref "U11") (pin "44") (pinfunction "(P0.27)_GPIO_44_44") (pintype "passive"))
    )
    (net (code "80") (name "unconnected-(U11-(P1.08)_GPIO_34-Pad34)") (class "Default")
      (node (ref "U11") (pin "34") (pinfunction "(P1.08)_GPIO_34_34") (pintype "passive"))
    )
    (net (code "81") (name "unconnected-(U11-(P1.09)_GPIO_33-Pad33)") (class "Default")
      (node (ref "U11") (pin "33") (pinfunction "(P1.09)_GPIO_33_33") (pintype "passive"))
    )
    (net (code "82") (name "unconnected-(U11-GPIO_16{slash}AIN1_(P0.03)'-Pad16)") (class "Default")
      (node (ref "U11") (pin "16") (pinfunction "GPIO_16/AIN1_(P0.03)'_16") (pintype "passive"))
    )
    (net (code "83") (name "unconnected-(U11-GPIO_17{slash}AIN4_(P0.28)'-Pad17)") (class "Default")
      (node (ref "U11") (pin "17") (pinfunction "GPIO_17/AIN4_(P0.28)'_17") (pintype "passive"))
    )
    (net (code "84") (name "unconnected-(U11-GPIO_18{slash}AIN0_(P0.02)'-Pad18)") (class "Default")
      (node (ref "U11") (pin "18") (pinfunction "GPIO_18/AIN0_(P0.02)'_18") (pintype "passive"))
    )
    (net (code "85") (name "unconnected-(U11-GPIO_22_(P1.13)'-Pad22)") (class "Default")
      (node (ref "U11") (pin "22") (pinfunction "GPIO_22_(P1.13)'_22") (pintype "passive"))
    )
    (net (code "86") (name "unconnected-(U11-GPIO_23{slash}AIN5_(P0.29)'-Pad23)") (class "Default")
      (node (ref "U11") (pin "23") (pinfunction "GPIO_23/AIN5_(P0.29)'_23") (pintype "passive"))
    )
    (net (code "87") (name "unconnected-(U11-GPIO_24{slash}AIN6_(P0.30)'-Pad24)") (class "Default")
      (node (ref "U11") (pin "24") (pinfunction "GPIO_24/AIN6_(P0.30)'_24") (pintype "passive"))
    )
    (net (code "88") (name "unconnected-(U11-GPIO_25{slash}AIN2_(P0.04)-Pad25)") (class "Default")
      (node (ref "U11") (pin "25") (pinfunction "GPIO_25/AIN2_(P0.04)_25") (pintype "passive"))
    )
    (net (code "89") (name "unconnected-(U11-GPIO_27{slash}AIN3_(P0.05)-Pad27)") (class "Default")
      (node (ref "U11") (pin "27") (pinfunction "GPIO_27/AIN3_(P0.05)_27") (pintype "passive"))
    )
    (net (code "90") (name "unconnected-(U11-GPIO_28{slash}NFC1_(P0.09)'-Pad28)") (class "Default")
      (node (ref "U11") (pin "28") (pinfunction "GPIO_28/NFC1_(P0.09)'_28") (pintype "passive"))
    )
    (net (code "91") (name "unconnected-(U11-GPIO_29{slash}NFC2_(P0.10)'-Pad29)") (class "Default")
      (node (ref "U11") (pin "29") (pinfunction "GPIO_29/NFC2_(P0.10)'_29") (pintype "passive"))
    )
    (net (code "92") (name "unconnected-(U12-EXTINT-Pad19)") (class "Default")
      (node (ref "U12") (pin "19") (pinfunction "EXTINT_19") (pintype "passive+no_connect"))
    )
    (net (code "93") (name "unconnected-(U12-RESET_N-Pad18)") (class "Default")
      (node (ref "U12") (pin "18") (pinfunction "RESET_N_18") (pintype "passive+no_connect"))
    )
    (net (code "94") (name "unconnected-(U12-SAFEBOOT_N-Pad8)") (class "Default")
      (node (ref "U12") (pin "8") (pinfunction "SAFEBOOT_N_8") (pintype "passive+no_connect"))
    )
    (net (code "95") (name "unconnected-(U12-TIMEPULSE-Pad7)") (class "Default")
      (node (ref "U12") (pin "7") (pinfunction "TIMEPULSE_7") (pintype "passive+no_connect"))
    )
    (net (code "96") (name "unconnected-(U15-NC-Pad3)") (class "Default")
      (node (ref "U15") (pin "3") (pinfunction "NC_3") (pintype "passive+no_connect"))
    )
    (net (code "97") (name "unconnected-(U15-NC-Pad8)") (class "Default")
      (node (ref "U15") (pin "8") (pinfunction "NC_8") (pintype "passive+no_connect"))
    )
    (net (code "98") (name "unconnected-(U15-NC-Pad13)") (class "Default")
      (node (ref "U15") (pin "13") (pinfunction "NC_13") (pintype "passive+no_connect"))
    )
    (net (code "99") (name "unconnected-(U15-NC-Pad15)") (class "Default")
      (node (ref "U15") (pin "15") (pinfunction "NC_15") (pintype "passive+no_connect"))
    )
    (net (code "100") (name "unconnected-(U15-NC-Pad16)") (class "Default")
      (node (ref "U15") (pin "16") (pinfunction "NC_16") (pintype "passive+no_connect"))
    )
    (net (code "101") (name "unconnected-(Z3-Pad0)") (class "Default")
      (node (ref "Z3") (pin "0") (pinfunction "0_0") (pintype "passive"))
    )
    (net (code "102") (name "unconnected-(Z4-Pad0)") (class "Default")
      (node (ref "Z4") (pin "0") (pinfunction "0_0") (pintype "passive"))
    )
  )
)
